# motor.net
KiCad netlist of a schematic drawn in Altium Designer
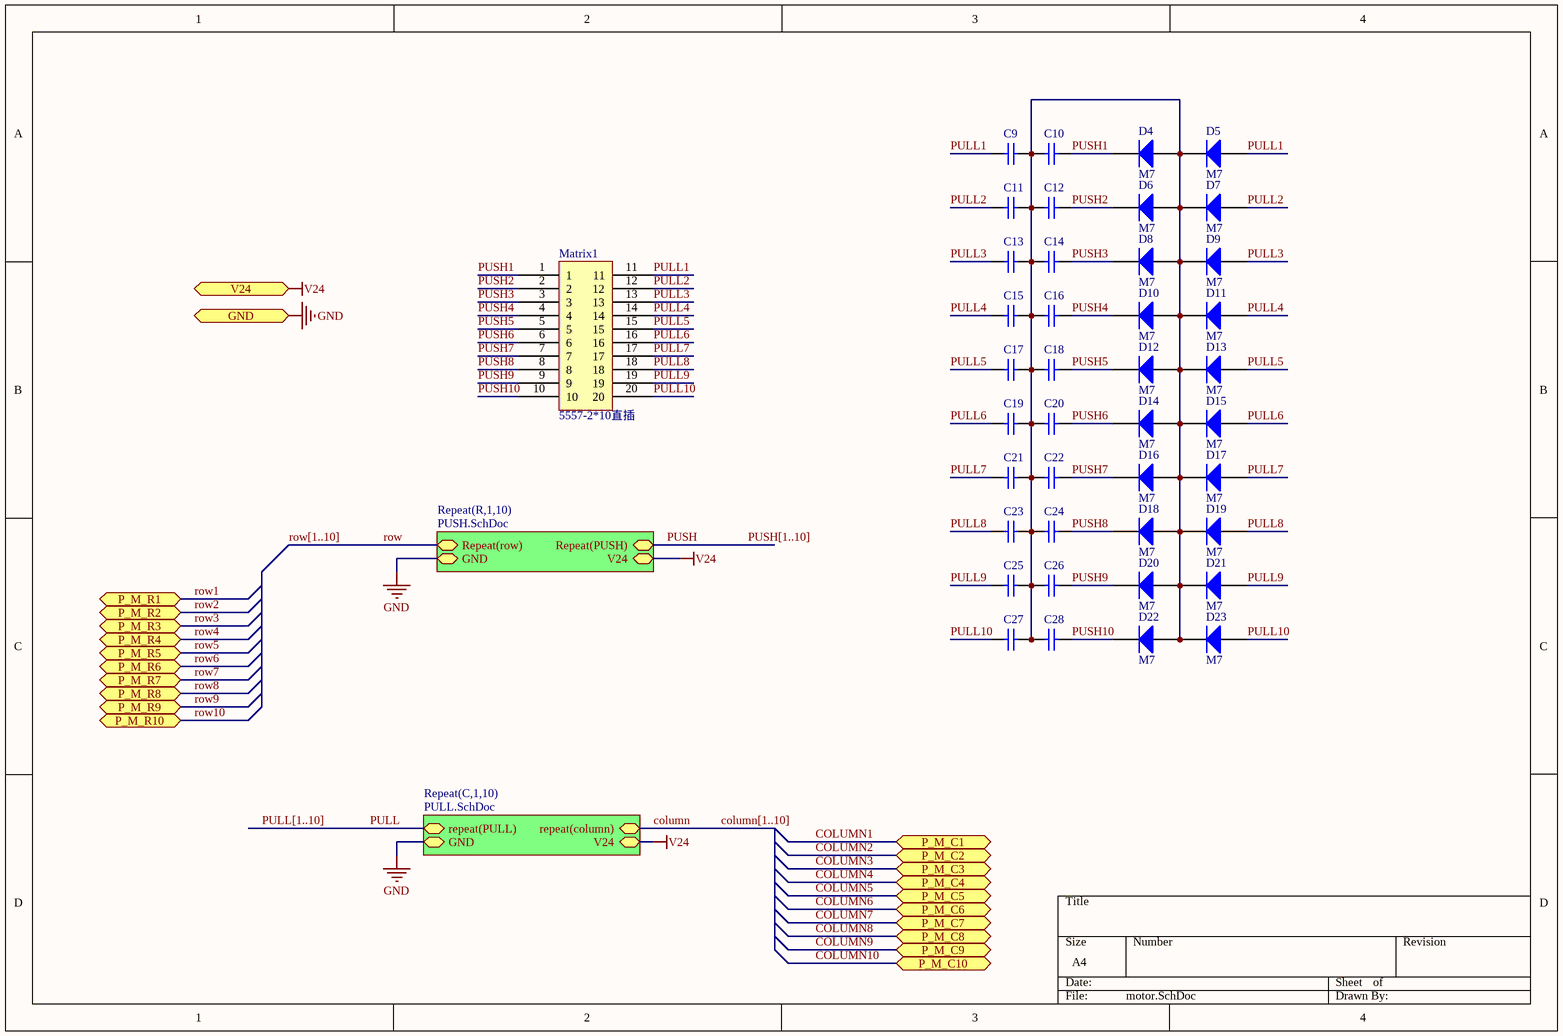
[diagram p0: motor.SchDoc]

(export (version "E")
  (design (tool "Eeschema 10.0.6"))
  (components
    (comp (ref "C9")
      (value "100nF(104) 10% 50V")
      (footprint "0805_C")
      (description "贴片电容")
      (libsource (lib "Miscellaneous Devices LC") (part "0805 100nF(104) 10% 50V"))
    )
    (comp (ref "C10")
      (value "100nF(104) 10% 50V")
      (footprint "0805_C")
      (description "贴片电容")
      (libsource (lib "Miscellaneous Devices LC") (part "0805 100nF(104) 10% 50V"))
    )
    (comp (ref "C11")
      (value "100nF(104) 10% 50V")
      (footprint "0805_C")
      (description "贴片电容")
      (libsource (lib "Miscellaneous Devices LC") (part "0805 100nF(104) 10% 50V"))
    )
    (comp (ref "C12")
      (value "100nF(104) 10% 50V")
      (footprint "0805_C")
      (description "贴片电容")
      (libsource (lib "Miscellaneous Devices LC") (part "0805 100nF(104) 10% 50V"))
    )
    (comp (ref "C13")
      (value "100nF(104) 10% 50V")
      (footprint "0805_C")
      (description "贴片电容")
      (libsource (lib "Miscellaneous Devices LC") (part "0805 100nF(104) 10% 50V"))
    )
    (comp (ref "C14")
      (value "100nF(104) 10% 50V")
      (footprint "0805_C")
      (description "贴片电容")
      (libsource (lib "Miscellaneous Devices LC") (part "0805 100nF(104) 10% 50V"))
    )
    (comp (ref "C15")
      (value "100nF(104) 10% 50V")
      (footprint "0805_C")
      (description "贴片电容")
      (libsource (lib "Miscellaneous Devices LC") (part "0805 100nF(104) 10% 50V"))
    )
    (comp (ref "C16")
      (value "100nF(104) 10% 50V")
      (footprint "0805_C")
      (description "贴片电容")
      (libsource (lib "Miscellaneous Devices LC") (part "0805 100nF(104) 10% 50V"))
    )
    (comp (ref "C17")
      (value "100nF(104) 10% 50V")
      (footprint "0805_C")
      (description "贴片电容")
      (libsource (lib "Miscellaneous Devices LC") (part "0805 100nF(104) 10% 50V"))
    )
    (comp (ref "C18")
      (value "100nF(104) 10% 50V")
      (footprint "0805_C")
      (description "贴片电容")
      (libsource (lib "Miscellaneous Devices LC") (part "0805 100nF(104) 10% 50V"))
    )
    (comp (ref "C19")
      (value "100nF(104) 10% 50V")
      (footprint "0805_C")
      (description "贴片电容")
      (libsource (lib "Miscellaneous Devices LC") (part "0805 100nF(104) 10% 50V"))
    )
    (comp (ref "C20")
      (value "100nF(104) 10% 50V")
      (footprint "0805_C")
      (description "贴片电容")
      (libsource (lib "Miscellaneous Devices LC") (part "0805 100nF(104) 10% 50V"))
    )
    (comp (ref "C21")
      (value "100nF(104) 10% 50V")
      (footprint "0805_C")
      (description "贴片电容")
      (libsource (lib "Miscellaneous Devices LC") (part "0805 100nF(104) 10% 50V"))
    )
    (comp (ref "C22")
      (value "100nF(104) 10% 50V")
      (footprint "0805_C")
      (description "贴片电容")
      (libsource (lib "Miscellaneous Devices LC") (part "0805 100nF(104) 10% 50V"))
    )
    (comp (ref "C23")
      (value "100nF(104) 10% 50V")
      (footprint "0805_C")
      (description "贴片电容")
      (libsource (lib "Miscellaneous Devices LC") (part "0805 100nF(104) 10% 50V"))
    )
    (comp (ref "C24")
      (value "100nF(104) 10% 50V")
      (footprint "0805_C")
      (description "贴片电容")
      (libsource (lib "Miscellaneous Devices LC") (part "0805 100nF(104) 10% 50V"))
    )
    (comp (ref "C25")
      (value "100nF(104) 10% 50V")
      (footprint "0805_C")
      (description "贴片电容")
      (libsource (lib "Miscellaneous Devices LC") (part "0805 100nF(104) 10% 50V"))
    )
    (comp (ref "C26")
      (value "100nF(104) 10% 50V")
      (footprint "0805_C")
      (description "贴片电容")
      (libsource (lib "Miscellaneous Devices LC") (part "0805 100nF(104) 10% 50V"))
    )
    (comp (ref "C27")
      (value "100nF(104) 10% 50V")
      (footprint "0805_C")
      (description "贴片电容")
      (libsource (lib "Miscellaneous Devices LC") (part "0805 100nF(104) 10% 50V"))
    )
    (comp (ref "C28")
      (value "100nF(104) 10% 50V")
      (footprint "0805_C")
      (description "贴片电容")
      (libsource (lib "Miscellaneous Devices LC") (part "0805 100nF(104) 10% 50V"))
    )
    (comp (ref "D4")
      (value "M7")
      (footprint "SMA(DO-214AC)_S1")
      (description "二极管")
      (libsource (lib "Miscellaneous Devices LC") (part "SMA(DO-214AC) M7"))
    )
    (comp (ref "D5")
      (value "M7")
      (footprint "SMA(DO-214AC)_S1")
      (description "二极管")
      (libsource (lib "Miscellaneous Devices LC") (part "SMA(DO-214AC) M7"))
    )
    (comp (ref "D6")
      (value "M7")
      (footprint "SMA(DO-214AC)_S1")
      (description "二极管")
      (libsource (lib "Miscellaneous Devices LC") (part "SMA(DO-214AC) M7"))
    )
    (comp (ref "D7")
      (value "M7")
      (footprint "SMA(DO-214AC)_S1")
      (description "二极管")
      (libsource (lib "Miscellaneous Devices LC") (part "SMA(DO-214AC) M7"))
    )
    (comp (ref "D8")
      (value "M7")
      (footprint "SMA(DO-214AC)_S1")
      (description "二极管")
      (libsource (lib "Miscellaneous Devices LC") (part "SMA(DO-214AC) M7"))
    )
    (comp (ref "D9")
      (value "M7")
      (footprint "SMA(DO-214AC)_S1")
      (description "二极管")
      (libsource (lib "Miscellaneous Devices LC") (part "SMA(DO-214AC) M7"))
    )
    (comp (ref "D10")
      (value "M7")
      (footprint "SMA(DO-214AC)_S1")
      (description "二极管")
      (libsource (lib "Miscellaneous Devices LC") (part "SMA(DO-214AC) M7"))
    )
    (comp (ref "D11")
      (value "M7")
      (footprint "SMA(DO-214AC)_S1")
      (description "二极管")
      (libsource (lib "Miscellaneous Devices LC") (part "SMA(DO-214AC) M7"))
    )
    (comp (ref "D12")
      (value "M7")
      (footprint "SMA(DO-214AC)_S1")
      (description "二极管")
      (libsource (lib "Miscellaneous Devices LC") (part "SMA(DO-214AC) M7"))
    )
    (comp (ref "D13")
      (value "M7")
      (footprint "SMA(DO-214AC)_S1")
      (description "二极管")
      (libsource (lib "Miscellaneous Devices LC") (part "SMA(DO-214AC) M7"))
    )
    (comp (ref "D14")
      (value "M7")
      (footprint "SMA(DO-214AC)_S1")
      (description "二极管")
      (libsource (lib "Miscellaneous Devices LC") (part "SMA(DO-214AC) M7"))
    )
    (comp (ref "D15")
      (value "M7")
      (footprint "SMA(DO-214AC)_S1")
      (description "二极管")
      (libsource (lib "Miscellaneous Devices LC") (part "SMA(DO-214AC) M7"))
    )
    (comp (ref "D16")
      (value "M7")
      (footprint "SMA(DO-214AC)_S1")
      (description "二极管")
      (libsource (lib "Miscellaneous Devices LC") (part "SMA(DO-214AC) M7"))
    )
    (comp (ref "D17")
      (value "M7")
      (footprint "SMA(DO-214AC)_S1")
      (description "二极管")
      (libsource (lib "Miscellaneous Devices LC") (part "SMA(DO-214AC) M7"))
    )
    (comp (ref "D18")
      (value "M7")
      (footprint "SMA(DO-214AC)_S1")
      (description "二极管")
      (libsource (lib "Miscellaneous Devices LC") (part "SMA(DO-214AC) M7"))
    )
    (comp (ref "D19")
      (value "M7")
      (footprint "SMA(DO-214AC)_S1")
      (description "二极管")
      (libsource (lib "Miscellaneous Devices LC") (part "SMA(DO-214AC) M7"))
    )
    (comp (ref "D20")
      (value "M7")
      (footprint "SMA(DO-214AC)_S1")
      (description "二极管")
      (libsource (lib "Miscellaneous Devices LC") (part "SMA(DO-214AC) M7"))
    )
    (comp (ref "D21")
      (value "M7")
      (footprint "SMA(DO-214AC)_S1")
      (description "二极管")
      (libsource (lib "Miscellaneous Devices LC") (part "SMA(DO-214AC) M7"))
    )
    (comp (ref "D22")
      (value "M7")
      (footprint "SMA(DO-214AC)_S1")
      (description "二极管")
      (libsource (lib "Miscellaneous Devices LC") (part "SMA(DO-214AC) M7"))
    )
    (comp (ref "D23")
      (value "M7")
      (footprint "SMA(DO-214AC)_S1")
      (description "二极管")
      (libsource (lib "Miscellaneous Devices LC") (part "SMA(DO-214AC) M7"))
    )
    (comp (ref "Matrix1")
      (value "5557-2*10直插")
      (footprint "5557_2*10")
      (libsource (lib "mylib") (part "5557-2*10直插"))
    )
  )
  (nets
    (net (code "22") (name "/PULL1") (class "Default")
      (node (ref "C9") (pin "1") (pinfunction "1_1") (pintype "passive"))
      (node (ref "D5") (pin "1") (pinfunction "A_1") (pintype "passive"))
      (node (ref "Matrix1") (pin "11") (pinfunction "11_11") (pintype "passive"))
    )
    (net (code "23") (name "/PULL2") (class "Default")
      (node (ref "C11") (pin "1") (pinfunction "1_1") (pintype "passive"))
      (node (ref "D7") (pin "1") (pinfunction "A_1") (pintype "passive"))
      (node (ref "Matrix1") (pin "12") (pinfunction "12_12") (pintype "passive"))
    )
    (net (code "24") (name "/PULL3") (class "Default")
      (node (ref "C13") (pin "1") (pinfunction "1_1") (pintype "passive"))
      (node (ref "D9") (pin "1") (pinfunction "A_1") (pintype "passive"))
      (node (ref "Matrix1") (pin "13") (pinfunction "13_13") (pintype "passive"))
    )
    (net (code "25") (name "/PULL4") (class "Default")
      (node (ref "C15") (pin "1") (pinfunction "1_1") (pintype "passive"))
      (node (ref "D11") (pin "1") (pinfunction "A_1") (pintype "passive"))
      (node (ref "Matrix1") (pin "14") (pinfunction "14_14") (pintype "passive"))
    )
    (net (code "26") (name "/PULL5") (class "Default")
      (node (ref "C17") (pin "1") (pinfunction "1_1") (pintype "passive"))
      (node (ref "D13") (pin "1") (pinfunction "A_1") (pintype "passive"))
      (node (ref "Matrix1") (pin "15") (pinfunction "15_15") (pintype "passive"))
    )
    (net (code "27") (name "/PULL6") (class "Default")
      (node (ref "C19") (pin "1") (pinfunction "1_1") (pintype "passive"))
      (node (ref "D15") (pin "1") (pinfunction "A_1") (pintype "passive"))
      (node (ref "Matrix1") (pin "16") (pinfunction "16_16") (pintype "passive"))
    )
    (net (code "28") (name "/PULL7") (class "Default")
      (node (ref "C21") (pin "1") (pinfunction "1_1") (pintype "passive"))
      (node (ref "D17") (pin "1") (pinfunction "A_1") (pintype "passive"))
      (node (ref "Matrix1") (pin "17") (pinfunction "17_17") (pintype "passive"))
    )
    (net (code "29") (name "/PULL8") (class "Default")
      (node (ref "C23") (pin "1") (pinfunction "1_1") (pintype "passive"))
      (node (ref "D19") (pin "1") (pinfunction "A_1") (pintype "passive"))
      (node (ref "Matrix1") (pin "18") (pinfunction "18_18") (pintype "passive"))
    )
    (net (code "30") (name "/PULL9") (class "Default")
      (node (ref "C25") (pin "1") (pinfunction "1_1") (pintype "passive"))
      (node (ref "D21") (pin "1") (pinfunction "A_1") (pintype "passive"))
      (node (ref "Matrix1") (pin "19") (pinfunction "19_19") (pintype "passive"))
    )
    (net (code "31") (name "/PULL10") (class "Default")
      (node (ref "C27") (pin "1") (pinfunction "1_1") (pintype "passive"))
      (node (ref "D23") (pin "1") (pinfunction "A_1") (pintype "passive"))
      (node (ref "Matrix1") (pin "20") (pinfunction "20_20") (pintype "passive"))
    )
    (net (code "34") (name "/PUSH1") (class "Default")
      (node (ref "C10") (pin "2") (pinfunction "2_2") (pintype "passive"))
      (node (ref "D4") (pin "2") (pinfunction "K_2") (pintype "passive"))
      (node (ref "Matrix1") (pin "1") (pinfunction "1_1") (pintype "passive"))
    )
    (net (code "35") (name "/PUSH2") (class "Default")
      (node (ref "C12") (pin "2") (pinfunction "2_2") (pintype "passive"))
      (node (ref "D6") (pin "2") (pinfunction "K_2") (pintype "passive"))
      (node (ref "Matrix1") (pin "2") (pinfunction "2_2") (pintype "passive"))
    )
    (net (code "36") (name "/PUSH3") (class "Default")
      (node (ref "C14") (pin "2") (pinfunction "2_2") (pintype "passive"))
      (node (ref "D8") (pin "2") (pinfunction "K_2") (pintype "passive"))
      (node (ref "Matrix1") (pin "3") (pinfunction "3_3") (pintype "passive"))
    )
    (net (code "37") (name "/PUSH4") (class "Default")
      (node (ref "C16") (pin "2") (pinfunction "2_2") (pintype "passive"))
      (node (ref "D10") (pin "2") (pinfunction "K_2") (pintype "passive"))
      (node (ref "Matrix1") (pin "4") (pinfunction "4_4") (pintype "passive"))
    )
    (net (code "38") (name "/PUSH5") (class "Default")
      (node (ref "C18") (pin "2") (pinfunction "2_2") (pintype "passive"))
      (node (ref "D12") (pin "2") (pinfunction "K_2") (pintype "passive"))
      (node (ref "Matrix1") (pin "5") (pinfunction "5_5") (pintype "passive"))
    )
    (net (code "39") (name "/PUSH6") (class "Default")
      (node (ref "C20") (pin "2") (pinfunction "2_2") (pintype "passive"))
      (node (ref "D14") (pin "2") (pinfunction "K_2") (pintype "passive"))
      (node (ref "Matrix1") (pin "6") (pinfunction "6_6") (pintype "passive"))
    )
    (net (code "40") (name "/PUSH7") (class "Default")
      (node (ref "C22") (pin "2") (pinfunction "2_2") (pintype "passive"))
      (node (ref "D16") (pin "2") (pinfunction "K_2") (pintype "passive"))
      (node (ref "Matrix1") (pin "7") (pinfunction "7_7") (pintype "passive"))
    )
    (net (code "41") (name "/PUSH8") (class "Default")
      (node (ref "C24") (pin "2") (pinfunction "2_2") (pintype "passive"))
      (node (ref "D18") (pin "2") (pinfunction "K_2") (pintype "passive"))
      (node (ref "Matrix1") (pin "8") (pinfunction "8_8") (pintype "passive"))
    )
    (net (code "42") (name "/PUSH9") (class "Default")
      (node (ref "C26") (pin "2") (pinfunction "2_2") (pintype "passive"))
      (node (ref "D20") (pin "2") (pinfunction "K_2") (pintype "passive"))
      (node (ref "Matrix1") (pin "9") (pinfunction "9_9") (pintype "passive"))
    )
    (net (code "43") (name "/PUSH10") (class "Default")
      (node (ref "C28") (pin "2") (pinfunction "2_2") (pintype "passive"))
      (node (ref "D22") (pin "2") (pinfunction "K_2") (pintype "passive"))
      (node (ref "Matrix1") (pin "10") (pinfunction "10_10") (pintype "passive"))
    )
    (net (code "60") (name "Net-(D10-A)") (class "Default")
      (node (ref "C10") (pin "1") (pinfunction "1_1") (pintype "passive"))
      (node (ref "C11") (pin "2") (pinfunction "2_2") (pintype "passive"))
      (node (ref "C12") (pin "1") (pinfunction "1_1") (pintype "passive"))
      (node (ref "C13") (pin "2") (pinfunction "2_2") (pintype "passive"))
      (node (ref "C14") (pin "1") (pinfunction "1_1") (pintype "passive"))
      (node (ref "C15") (pin "2") (pinfunction "2_2") (pintype "passive"))
      (node (ref "C16") (pin "1") (pinfunction "1_1") (pintype "passive"))
      (node (ref "C17") (pin "2") (pinfunction "2_2") (pintype "passive"))
      (node (ref "C18") (pin "1") (pinfunction "1_1") (pintype "passive"))
      (node (ref "C19") (pin "2") (pinfunction "2_2") (pintype "passive"))
      (node (ref "C20") (pin "1") (pinfunction "1_1") (pintype "passive"))
      (node (ref "C21") (pin "2") (pinfunction "2_2") (pintype "passive"))
      (node (ref "C22") (pin "1") (pinfunction "1_1") (pintype "passive"))
      (node (ref "C23") (pin "2") (pinfunction "2_2") (pintype "passive"))
      (node (ref "C24") (pin "1") (pinfunction "1_1") (pintype "passive"))
      (node (ref "C25") (pin "2") (pinfunction "2_2") (pintype "passive"))
      (node (ref "C26") (pin "1") (pinfunction "1_1") (pintype "passive"))
      (node (ref "C27") (pin "2") (pinfunction "2_2") (pintype "passive"))
      (node (ref "C28") (pin "1") (pinfunction "1_1") (pintype "passive"))
      (node (ref "C9") (pin "2") (pinfunction "2_2") (pintype "passive"))
      (node (ref "D10") (pin "1") (pinfunction "A_1") (pintype "passive"))
      (node (ref "D11") (pin "2") (pinfunction "K_2") (pintype "passive"))
      (node (ref "D12") (pin "1") (pinfunction "A_1") (pintype "passive"))
      (node (ref "D13") (pin "2") (pinfunction "K_2") (pintype "passive"))
      (node (ref "D14") (pin "1") (pinfunction "A_1") (pintype "passive"))
      (node (ref "D15") (pin "2") (pinfunction "K_2") (pintype "passive"))
      (node (ref "D16") (pin "1") (pinfunction "A_1") (pintype "passive"))
      (node (ref "D17") (pin "2") (pinfunction "K_2") (pintype "passive"))
      (node (ref "D18") (pin "1") (pinfunction "A_1") (pintype "passive"))
      (node (ref "D19") (pin "2") (pinfunction "K_2") (pintype "passive"))
      (node (ref "D20") (pin "1") (pinfunction "A_1") (pintype "passive"))
      (node (ref "D21") (pin "2") (pinfunction "K_2") (pintype "passive"))
      (node (ref "D22") (pin "1") (pinfunction "A_1") (pintype "passive"))
      (node (ref "D23") (pin "2") (pinfunction "K_2") (pintype "passive"))
      (node (ref "D4") (pin "1") (pinfunction "A_1") (pintype "passive"))
      (node (ref "D5") (pin "2") (pinfunction "K_2") (pintype "passive"))
      (node (ref "D6") (pin "1") (pinfunction "A_1") (pintype "passive"))
      (node (ref "D7") (pin "2") (pinfunction "K_2") (pintype "passive"))
      (node (ref "D8") (pin "1") (pinfunction "A_1") (pintype "passive"))
      (node (ref "D9") (pin "2") (pinfunction "K_2") (pintype "passive"))
    )
  )
)
